# caton-d-q100.net
KiCad netlist of a schematic drawn in Altium Designer
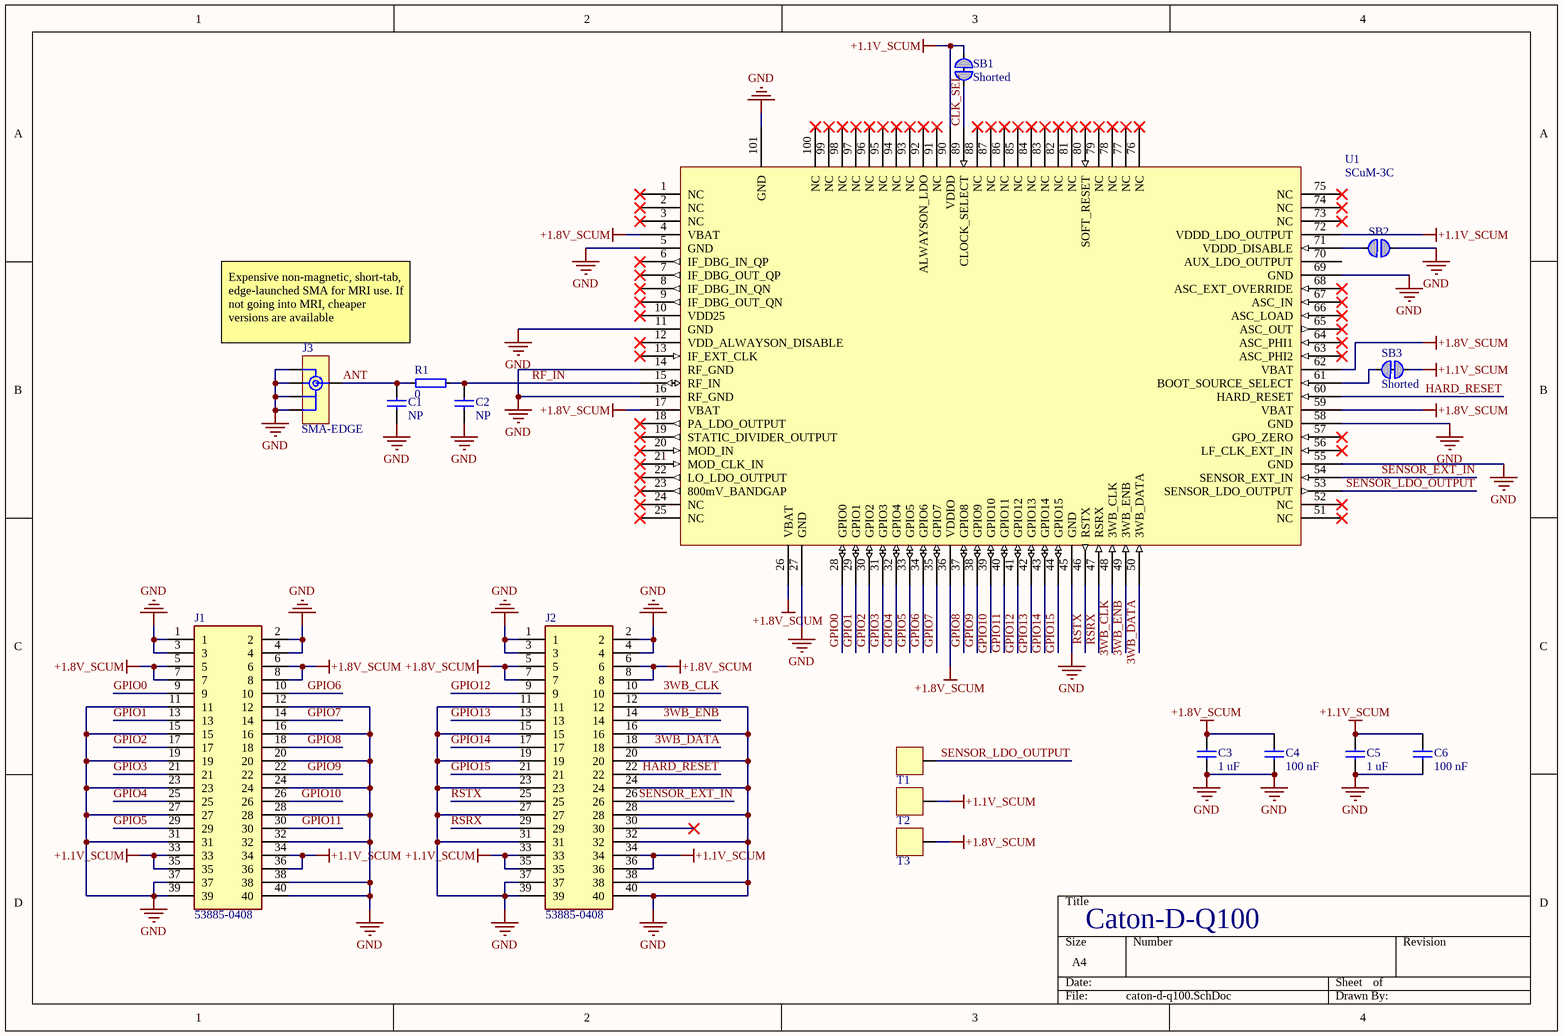
[diagram p0: caton-d-q100.SchDoc]

(export (version "E")
  (design (tool "Eeschema 10.0.6"))
  (components
    (comp (ref "C1")
      (value "NP")
      (footprint "BWRC:0603")
      (description "Capacitor, 0603, X5R, ±10%")
      (fields
        (field (name "PART NUMBER") "C0603-4µ7")
        (field (name "MANUFACTURER") "N.A.")
        (field (name "AUTHOR") "rsk")
      )
      (libsource (lib "BSAC") (part "C0603"))
    )
    (comp (ref "C2")
      (value "NP")
      (footprint "BWRC:0603")
      (description "Capacitor, 0603, X5R, ±10%")
      (fields
        (field (name "PART NUMBER") "C0603-4µ7")
        (field (name "MANUFACTURER") "N.A.")
        (field (name "AUTHOR") "rsk")
      )
      (libsource (lib "BSAC") (part "C0603"))
    )
    (comp (ref "C3")
      (value "1 uF")
      (footprint "BWRC:0603")
      (description "Capacitor, 0603, X5R, ±10%")
      (fields
        (field (name "PART NUMBER") "C0603-4µ7")
        (field (name "MANUFACTURER") "N.A.")
        (field (name "AUTHOR") "rsk")
      )
      (libsource (lib "BSAC") (part "C0603"))
    )
    (comp (ref "C4")
      (value "100 nF")
      (footprint "BWRC:0603")
      (description "Capacitor, 0603, X5R, ±10%")
      (fields
        (field (name "PART NUMBER") "C0603-4µ7")
        (field (name "MANUFACTURER") "N.A.")
        (field (name "AUTHOR") "rsk")
      )
      (libsource (lib "BSAC") (part "C0603"))
    )
    (comp (ref "C5")
      (value "1 uF")
      (footprint "BWRC:0603")
      (description "Capacitor, 0603, X5R, ±10%")
      (fields
        (field (name "PART NUMBER") "C0603-4µ7")
        (field (name "MANUFACTURER") "N.A.")
        (field (name "AUTHOR") "rsk")
      )
      (libsource (lib "BSAC") (part "C0603"))
    )
    (comp (ref "C6")
      (value "100 nF")
      (footprint "BWRC:0603")
      (description "Capacitor, 0603, X5R, ±10%")
      (fields
        (field (name "PART NUMBER") "C0603-4µ7")
        (field (name "MANUFACTURER") "N.A.")
        (field (name "AUTHOR") "rsk")
      )
      (libsource (lib "BSAC") (part "C0603"))
    )
    (comp (ref "J1")
      (value "53885-0408")
      (footprint "SamacSys:538850408")
      (fields (field (name "MOUSER PART NUMBER") "538-53885-0408"))
      (libsource (lib "BSAC") (part "53885-0408"))
    )
    (comp (ref "J2")
      (value "53885-0408")
      (footprint "SamacSys:538850408")
      (fields (field (name "MOUSER PART NUMBER") "538-53885-0408"))
      (libsource (lib "BSAC") (part "53885-0408"))
    )
    (comp (ref "J3")
      (value "SMA-EDGE")
      (footprint "BSAC:RF2-143-T-17-50-G")
      (description "Non-Magnetic\r\nCONN SMA JACK STR 50OHM EDGE MNT")
      (libsource (lib "BSAC") (part "SMA-EDGE"))
    )
    (comp (ref "R1")
      (value "0")
      (footprint "BWRC:0603")
      (description "Resistor, 0603")
      (fields
        (field (name "PART NUMBER") "R0201-10k")
        (field (name "MANUFACTURER") "N.A.")
        (field (name "AUTHOR") "rsk")
      )
      (libsource (lib "BSAC") (part "R0603"))
    )
    (comp (ref "SB1")
      (value "Shorted")
      (footprint "BSAC:Solderbridge_Shorted")
      (description "Shorted Solderbridge")
      (fields
        (field (name "PART NUMBER") "Solderbridge Shorted")
        (field (name "MANUFACTURER") "N.A.")
        (field (name "AUTHOR") "rsk")
      )
      (libsource (lib "BSAC") (part "Solderbridge Shorted"))
    )
    (comp (ref "SB2")
      (value "Solderbridge")
      (footprint "Solderbridge")
      (fields (field (name "MANUFACTURER") "N.A.") (field (name "AUTHOR") "rsk"))
      (libsource (lib "BSAC") (part "SOLDERBRIDGE"))
    )
    (comp (ref "SB3")
      (value "Shorted")
      (footprint "BSAC:Solderbridge_Shorted")
      (description "Shorted Solderbridge")
      (fields
        (field (name "PART NUMBER") "Solderbridge Shorted")
        (field (name "MANUFACTURER") "N.A.")
        (field (name "AUTHOR") "rsk")
      )
      (libsource (lib "BSAC") (part "Solderbridge Shorted"))
    )
    (comp (ref "T1")
      (value "TP_VIA")
      (footprint "BSAC:TP_VIA_1MM")
      (description "Test point 1 pin")
      (libsource (lib "BSAC") (part "TP_VIA"))
    )
    (comp (ref "T2")
      (value "TP_VIA")
      (footprint "BSAC:TP_VIA_1MM")
      (description "Test point 1 pin")
      (libsource (lib "BSAC") (part "TP_VIA"))
    )
    (comp (ref "T3")
      (value "TP_VIA")
      (footprint "BSAC:TP_VIA_1MM")
      (description "Test point 1 pin")
      (libsource (lib "BSAC") (part "TP_VIA"))
    )
    (comp (ref "U1")
      (value "SCuM-3C")
      (footprint "BSAC:QFN40P1200X1200X100_HS-101N")
      (libsource (lib "BSAC") (part "SCuM-3C"))
    )
  )
  (nets
    (net (code "1") (name "+1.1V_SCUM") (class "Default")
      (node (ref "C5") (pin "2") (pinfunction "2_2") (pintype "passive"))
      (node (ref "C6") (pin "2") (pinfunction "2_2") (pintype "passive"))
      (node (ref "J1") (pin "33") (pinfunction "33_33") (pintype "passive"))
      (node (ref "J1") (pin "34") (pinfunction "34_34") (pintype "passive"))
      (node (ref "J1") (pin "35") (pinfunction "35_35") (pintype "passive"))
      (node (ref "J1") (pin "36") (pinfunction "36_36") (pintype "passive"))
      (node (ref "J2") (pin "33") (pinfunction "33_33") (pintype "passive"))
      (node (ref "J2") (pin "34") (pinfunction "34_34") (pintype "passive"))
      (node (ref "J2") (pin "35") (pinfunction "35_35") (pintype "passive"))
      (node (ref "J2") (pin "36") (pinfunction "36_36") (pintype "passive"))
      (node (ref "SB1") (pin "1") (pinfunction "0_1") (pintype "passive"))
      (node (ref "SB3") (pin "2") (pinfunction "1_2") (pintype "passive"))
      (node (ref "T2") (pin "1") (pinfunction "1_1") (pintype "passive"))
      (node (ref "U1") (pin "72") (pinfunction "VDDD_LDO_OUTPUT_72") (pintype "power_in"))
      (node (ref "U1") (pin "90") (pinfunction "VDDD_90") (pintype "power_in"))
    )
    (net (code "2") (name "+1.8V_SCUM") (class "Default")
      (node (ref "C3") (pin "2") (pinfunction "2_2") (pintype "passive"))
      (node (ref "C4") (pin "2") (pinfunction "2_2") (pintype "passive"))
      (node (ref "J1") (pin "5") (pinfunction "5_5") (pintype "passive"))
      (node (ref "J1") (pin "6") (pinfunction "6_6") (pintype "passive"))
      (node (ref "J1") (pin "7") (pinfunction "7_7") (pintype "passive"))
      (node (ref "J1") (pin "8") (pinfunction "8_8") (pintype "passive"))
      (node (ref "J2") (pin "5") (pinfunction "5_5") (pintype "passive"))
      (node (ref "J2") (pin "6") (pinfunction "6_6") (pintype "passive"))
      (node (ref "J2") (pin "7") (pinfunction "7_7") (pintype "passive"))
      (node (ref "J2") (pin "8") (pinfunction "8_8") (pintype "passive"))
      (node (ref "T3") (pin "1") (pinfunction "1_1") (pintype "passive"))
      (node (ref "U1") (pin "17") (pinfunction "VBAT_17") (pintype "power_in"))
      (node (ref "U1") (pin "26") (pinfunction "VBAT_26") (pintype "power_in"))
      (node (ref "U1") (pin "36") (pinfunction "VDDIO_36") (pintype "power_in"))
      (node (ref "U1") (pin "4") (pinfunction "VBAT_4") (pintype "power_in"))
      (node (ref "U1") (pin "59") (pinfunction "VBAT_59") (pintype "power_in"))
      (node (ref "U1") (pin "62") (pinfunction "VBAT_62") (pintype "power_in"))
    )
    (net (code "3") (name "/3WB_CLK") (class "Default")
      (node (ref "J2") (pin "10") (pinfunction "10_10") (pintype "passive"))
      (node (ref "U1") (pin "48") (pinfunction "3WB_CLK_48") (pintype "input"))
    )
    (net (code "4") (name "/3WB_DATA") (class "Default")
      (node (ref "J2") (pin "18") (pinfunction "18_18") (pintype "passive"))
      (node (ref "U1") (pin "50") (pinfunction "3WB_DATA_50") (pintype "input"))
    )
    (net (code "5") (name "/3WB_ENB") (class "Default")
      (node (ref "J2") (pin "14") (pinfunction "14_14") (pintype "passive"))
      (node (ref "U1") (pin "49") (pinfunction "3WB_ENB_49") (pintype "input"))
    )
    (net (code "6") (name "/ANT") (class "Default")
      (node (ref "C1") (pin "2") (pinfunction "2_2") (pintype "passive"))
      (node (ref "J3") (pin "1") (pinfunction "1_1") (pintype "passive"))
      (node (ref "R1") (pin "1") (pinfunction "1_1") (pintype "passive"))
    )
    (net (code "7") (name "/CLK_SEL") (class "Default")
      (node (ref "SB1") (pin "2") (pinfunction "1_2") (pintype "passive"))
      (node (ref "U1") (pin "89") (pinfunction "CLOCK_SELECT_89") (pintype "input"))
    )
    (net (code "8") (name "/GPIO0") (class "Default")
      (node (ref "J1") (pin "9") (pinfunction "9_9") (pintype "passive"))
      (node (ref "U1") (pin "28") (pinfunction "GPIO0_28") (pintype "bidirectional"))
    )
    (net (code "9") (name "/GPIO1") (class "Default")
      (node (ref "J1") (pin "13") (pinfunction "13_13") (pintype "passive"))
      (node (ref "U1") (pin "29") (pinfunction "GPIO1_29") (pintype "bidirectional"))
    )
    (net (code "10") (name "/GPIO2") (class "Default")
      (node (ref "J1") (pin "17") (pinfunction "17_17") (pintype "passive"))
      (node (ref "U1") (pin "30") (pinfunction "GPIO2_30") (pintype "bidirectional"))
    )
    (net (code "11") (name "/GPIO3") (class "Default")
      (node (ref "J1") (pin "21") (pinfunction "21_21") (pintype "passive"))
      (node (ref "U1") (pin "31") (pinfunction "GPIO3_31") (pintype "bidirectional"))
    )
    (net (code "12") (name "/GPIO4") (class "Default")
      (node (ref "J1") (pin "25") (pinfunction "25_25") (pintype "passive"))
      (node (ref "U1") (pin "32") (pinfunction "GPIO4_32") (pintype "bidirectional"))
    )
    (net (code "13") (name "/GPIO5") (class "Default")
      (node (ref "J1") (pin "29") (pinfunction "29_29") (pintype "passive"))
      (node (ref "U1") (pin "33") (pinfunction "GPIO5_33") (pintype "bidirectional"))
    )
    (net (code "14") (name "/GPIO6") (class "Default")
      (node (ref "J1") (pin "10") (pinfunction "10_10") (pintype "passive"))
      (node (ref "U1") (pin "34") (pinfunction "GPIO6_34") (pintype "bidirectional"))
    )
    (net (code "15") (name "/GPIO7") (class "Default")
      (node (ref "J1") (pin "14") (pinfunction "14_14") (pintype "passive"))
      (node (ref "U1") (pin "35") (pinfunction "GPIO7_35") (pintype "bidirectional"))
    )
    (net (code "16") (name "/GPIO8") (class "Default")
      (node (ref "J1") (pin "18") (pinfunction "18_18") (pintype "passive"))
      (node (ref "U1") (pin "37") (pinfunction "GPIO8_37") (pintype "bidirectional"))
    )
    (net (code "17") (name "/GPIO9") (class "Default")
      (node (ref "J1") (pin "22") (pinfunction "22_22") (pintype "passive"))
      (node (ref "U1") (pin "38") (pinfunction "GPIO9_38") (pintype "bidirectional"))
    )
    (net (code "18") (name "/GPIO10") (class "Default")
      (node (ref "J1") (pin "26") (pinfunction "26_26") (pintype "passive"))
      (node (ref "U1") (pin "39") (pinfunction "GPIO10_39") (pintype "bidirectional"))
    )
    (net (code "19") (name "/GPIO11") (class "Default")
      (node (ref "J1") (pin "30") (pinfunction "30_30") (pintype "passive"))
      (node (ref "U1") (pin "40") (pinfunction "GPIO11_40") (pintype "bidirectional"))
    )
    (net (code "20") (name "/GPIO12") (class "Default")
      (node (ref "J2") (pin "9") (pinfunction "9_9") (pintype "passive"))
      (node (ref "U1") (pin "41") (pinfunction "GPIO12_41") (pintype "bidirectional"))
    )
    (net (code "21") (name "/GPIO13") (class "Default")
      (node (ref "J2") (pin "13") (pinfunction "13_13") (pintype "passive"))
      (node (ref "U1") (pin "42") (pinfunction "GPIO13_42") (pintype "bidirectional"))
    )
    (net (code "22") (name "/GPIO14") (class "Default")
      (node (ref "J2") (pin "17") (pinfunction "17_17") (pintype "passive"))
      (node (ref "U1") (pin "43") (pinfunction "GPIO14_43") (pintype "bidirectional"))
    )
    (net (code "23") (name "/GPIO15") (class "Default")
      (node (ref "J2") (pin "21") (pinfunction "21_21") (pintype "passive"))
      (node (ref "U1") (pin "44") (pinfunction "GPIO15_44") (pintype "bidirectional"))
    )
    (net (code "24") (name "/HARD_RESET") (class "Default")
      (node (ref "J2") (pin "22") (pinfunction "22_22") (pintype "passive"))
      (node (ref "U1") (pin "60") (pinfunction "HARD_RESET_60") (pintype "input"))
    )
    (net (code "25") (name "/RF_IN") (class "Default")
      (node (ref "C2") (pin "2") (pinfunction "2_2") (pintype "passive"))
      (node (ref "R1") (pin "2") (pinfunction "2_2") (pintype "passive"))
      (node (ref "U1") (pin "15") (pinfunction "RF_IN_15") (pintype "bidirectional"))
    )
    (net (code "26") (name "/RSRX") (class "Default")
      (node (ref "J2") (pin "29") (pinfunction "29_29") (pintype "passive"))
      (node (ref "U1") (pin "47") (pinfunction "RSRX_47") (pintype "input"))
    )
    (net (code "27") (name "/RSTX") (class "Default")
      (node (ref "J2") (pin "25") (pinfunction "25_25") (pintype "passive"))
      (node (ref "U1") (pin "46") (pinfunction "RSTX_46") (pintype "output"))
    )
    (net (code "28") (name "/SENSOR_EXT_IN") (class "Default")
      (node (ref "J2") (pin "26") (pinfunction "26_26") (pintype "passive"))
      (node (ref "U1") (pin "54") (pinfunction "SENSOR_EXT_IN_54") (pintype "input"))
    )
    (net (code "29") (name "/SENSOR_LDO_OUTPUT") (class "Default")
      (node (ref "T1") (pin "1") (pinfunction "1_1") (pintype "passive"))
      (node (ref "U1") (pin "53") (pinfunction "SENSOR_LDO_OUTPUT_53") (pintype "output"))
    )
    (net (code "30") (name "GND") (class "Default")
      (node (ref "C1") (pin "1") (pinfunction "1_1") (pintype "passive"))
      (node (ref "C2") (pin "1") (pinfunction "1_1") (pintype "passive"))
      (node (ref "C3") (pin "1") (pinfunction "1_1") (pintype "passive"))
      (node (ref "C4") (pin "1") (pinfunction "1_1") (pintype "passive"))
      (node (ref "C5") (pin "1") (pinfunction "1_1") (pintype "passive"))
      (node (ref "C6") (pin "1") (pinfunction "1_1") (pintype "passive"))
      (node (ref "J1") (pin "1") (pinfunction "1_1") (pintype "passive"))
      (node (ref "J1") (pin "11") (pinfunction "11_11") (pintype "passive"))
      (node (ref "J1") (pin "12") (pinfunction "12_12") (pintype "passive"))
      (node (ref "J1") (pin "15") (pinfunction "15_15") (pintype "passive"))
      (node (ref "J1") (pin "16") (pinfunction "16_16") (pintype "passive"))
      (node (ref "J1") (pin "19") (pinfunction "19_19") (pintype "passive"))
      (node (ref "J1") (pin "2") (pinfunction "2_2") (pintype "passive"))
      (node (ref "J1") (pin "20") (pinfunction "20_20") (pintype "passive"))
      (node (ref "J1") (pin "23") (pinfunction "23_23") (pintype "passive"))
      (node (ref "J1") (pin "24") (pinfunction "24_24") (pintype "passive"))
      (node (ref "J1") (pin "27") (pinfunction "27_27") (pintype "passive"))
      (node (ref "J1") (pin "28") (pinfunction "28_28") (pintype "passive"))
      (node (ref "J1") (pin "3") (pinfunction "3_3") (pintype "passive"))
      (node (ref "J1") (pin "31") (pinfunction "31_31") (pintype "passive"))
      (node (ref "J1") (pin "32") (pinfunction "32_32") (pintype "passive"))
      (node (ref "J1") (pin "37") (pinfunction "37_37") (pintype "passive"))
      (node (ref "J1") (pin "38") (pinfunction "38_38") (pintype "passive"))
      (node (ref "J1") (pin "39") (pinfunction "39_39") (pintype "passive"))
      (node (ref "J1") (pin "4") (pinfunction "4_4") (pintype "passive"))
      (node (ref "J1") (pin "40") (pinfunction "40_40") (pintype "passive"))
      (node (ref "J2") (pin "1") (pinfunction "1_1") (pintype "passive"))
      (node (ref "J2") (pin "11") (pinfunction "11_11") (pintype "passive"))
      (node (ref "J2") (pin "12") (pinfunction "12_12") (pintype "passive"))
      (node (ref "J2") (pin "15") (pinfunction "15_15") (pintype "passive"))
      (node (ref "J2") (pin "16") (pinfunction "16_16") (pintype "passive"))
      (node (ref "J2") (pin "19") (pinfunction "19_19") (pintype "passive"))
      (node (ref "J2") (pin "2") (pinfunction "2_2") (pintype "passive"))
      (node (ref "J2") (pin "20") (pinfunction "20_20") (pintype "passive"))
      (node (ref "J2") (pin "23") (pinfunction "23_23") (pintype "passive"))
      (node (ref "J2") (pin "24") (pinfunction "24_24") (pintype "passive"))
      (node (ref "J2") (pin "27") (pinfunction "27_27") (pintype "passive"))
      (node (ref "J2") (pin "28") (pinfunction "28_28") (pintype "passive"))
      (node (ref "J2") (pin "3") (pinfunction "3_3") (pintype "passive"))
      (node (ref "J2") (pin "31") (pinfunction "31_31") (pintype "passive"))
      (node (ref "J2") (pin "32") (pinfunction "32_32") (pintype "passive"))
      (node (ref "J2") (pin "37") (pinfunction "37_37") (pintype "passive"))
      (node (ref "J2") (pin "38") (pinfunction "38_38") (pintype "passive"))
      (node (ref "J2") (pin "39") (pinfunction "39_39") (pintype "passive"))
      (node (ref "J2") (pin "4") (pinfunction "4_4") (pintype "passive"))
      (node (ref "J2") (pin "40") (pinfunction "40_40") (pintype "passive"))
      (node (ref "J3") (pin "2") (pinfunction "2_2") (pintype "passive"))
      (node (ref "J3") (pin "3") (pinfunction "3_3") (pintype "passive"))
      (node (ref "J3") (pin "4") (pinfunction "4_4") (pintype "passive"))
      (node (ref "J3") (pin "5") (pinfunction "5_5") (pintype "passive"))
      (node (ref "SB2") (pin "2") (pinfunction "1_2") (pintype "passive"))
      (node (ref "U1") (pin "101") (pinfunction "GND_101") (pintype "power_in"))
      (node (ref "U1") (pin "11") (pinfunction "GND_11") (pintype "power_in"))
      (node (ref "U1") (pin "14") (pinfunction "RF_GND_14") (pintype "power_in"))
      (node (ref "U1") (pin "16") (pinfunction "RF_GND_16") (pintype "power_in"))
      (node (ref "U1") (pin "27") (pinfunction "GND_27") (pintype "power_in"))
      (node (ref "U1") (pin "45") (pinfunction "GND_45") (pintype "power_in"))
      (node (ref "U1") (pin "5") (pinfunction "GND_5") (pintype "power_in"))
      (node (ref "U1") (pin "55") (pinfunction "GND_55") (pintype "power_in"))
      (node (ref "U1") (pin "58") (pinfunction "GND_58") (pintype "power_in"))
      (node (ref "U1") (pin "69") (pinfunction "GND_69") (pintype "power_in"))
    )
    (net (code "31") (name "Net-(SB2-0)") (class "Default")
      (node (ref "SB2") (pin "1") (pinfunction "0_1") (pintype "passive"))
      (node (ref "U1") (pin "71") (pinfunction "VDDD_DISABLE_71") (pintype "input"))
    )
    (net (code "32") (name "Net-(SB3-0)") (class "Default")
      (node (ref "SB3") (pin "1") (pinfunction "0_1") (pintype "passive"))
      (node (ref "U1") (pin "61") (pinfunction "BOOT_SOURCE_SELECT_61") (pintype "input"))
    )
    (net (code "33") (name "unconnected-(J2-Pad30)") (class "Default")
      (node (ref "J2") (pin "30") (pinfunction "30_30") (pintype "passive+no_connect"))
    )
    (net (code "34") (name "unconnected-(U1-800mV_BANDGAP-Pad23)") (class "Default")
      (node (ref "U1") (pin "23") (pinfunction "800mV_BANDGAP_23") (pintype "output+no_connect"))
    )
    (net (code "35") (name "unconnected-(U1-ALWAYSON_LDO-Pad92)") (class "Default")
      (node (ref "U1") (pin "92") (pinfunction "ALWAYSON_LDO_92") (pintype "power_in+no_connect"))
    )
    (net (code "36") (name "unconnected-(U1-ASC_EXT_OVERRIDE-Pad68)") (class "Default")
      (node (ref "U1") (pin "68") (pinfunction "ASC_EXT_OVERRIDE_68") (pintype "input+no_connect"))
    )
    (net (code "37") (name "unconnected-(U1-ASC_IN-Pad67)") (class "Default")
      (node (ref "U1") (pin "67") (pinfunction "ASC_IN_67") (pintype "input+no_connect"))
    )
    (net (code "38") (name "unconnected-(U1-ASC_LOAD-Pad66)") (class "Default")
      (node (ref "U1") (pin "66") (pinfunction "ASC_LOAD_66") (pintype "input+no_connect"))
    )
    (net (code "39") (name "unconnected-(U1-ASC_OUT-Pad65)") (class "Default")
      (node (ref "U1") (pin "65") (pinfunction "ASC_OUT_65") (pintype "output+no_connect"))
    )
    (net (code "40") (name "unconnected-(U1-ASC_PHI1-Pad64)") (class "Default")
      (node (ref "U1") (pin "64") (pinfunction "ASC_PHI1_64") (pintype "input+no_connect"))
    )
    (net (code "41") (name "unconnected-(U1-ASC_PHI2-Pad63)") (class "Default")
      (node (ref "U1") (pin "63") (pinfunction "ASC_PHI2_63") (pintype "input+no_connect"))
    )
    (net (code "42") (name "unconnected-(U1-AUX_LDO_OUTPUT-Pad70)") (class "Default")
      (node (ref "U1") (pin "70") (pinfunction "AUX_LDO_OUTPUT_70") (pintype "power_in"))
    )
    (net (code "43") (name "unconnected-(U1-GPO_ZERO-Pad57)") (class "Default")
      (node (ref "U1") (pin "57") (pinfunction "GPO_ZERO_57") (pintype "input+no_connect"))
    )
    (net (code "44") (name "unconnected-(U1-IF_DBG_IN_QN-Pad8)") (class "Default")
      (node (ref "U1") (pin "8") (pinfunction "IF_DBG_IN_QN_8") (pintype "output+no_connect"))
    )
    (net (code "45") (name "unconnected-(U1-IF_DBG_IN_QP-Pad6)") (class "Default")
      (node (ref "U1") (pin "6") (pinfunction "IF_DBG_IN_QP_6") (pintype "output+no_connect"))
    )
    (net (code "46") (name "unconnected-(U1-IF_DBG_OUT_QN-Pad9)") (class "Default")
      (node (ref "U1") (pin "9") (pinfunction "IF_DBG_OUT_QN_9") (pintype "output+no_connect"))
    )
    (net (code "47") (name "unconnected-(U1-IF_DBG_OUT_QP-Pad7)") (class "Default")
      (node (ref "U1") (pin "7") (pinfunction "IF_DBG_OUT_QP_7") (pintype "output+no_connect"))
    )
    (net (code "48") (name "unconnected-(U1-IF_EXT_CLK-Pad13)") (class "Default")
      (node (ref "U1") (pin "13") (pinfunction "IF_EXT_CLK_13") (pintype "input+no_connect"))
    )
    (net (code "49") (name "unconnected-(U1-LF_CLK_EXT_IN-Pad56)") (class "Default")
      (node (ref "U1") (pin "56") (pinfunction "LF_CLK_EXT_IN_56") (pintype "input+no_connect"))
    )
    (net (code "50") (name "unconnected-(U1-LO_LDO_OUTPUT-Pad22)") (class "Default")
      (node (ref "U1") (pin "22") (pinfunction "LO_LDO_OUTPUT_22") (pintype "output+no_connect"))
    )
    (net (code "51") (name "unconnected-(U1-MOD_CLK_IN-Pad21)") (class "Default")
      (node (ref "U1") (pin "21") (pinfunction "MOD_CLK_IN_21") (pintype "input+no_connect"))
    )
    (net (code "52") (name "unconnected-(U1-MOD_IN-Pad20)") (class "Default")
      (node (ref "U1") (pin "20") (pinfunction "MOD_IN_20") (pintype "input+no_connect"))
    )
    (net (code "53") (name "unconnected-(U1-NC-Pad1)") (class "Default")
      (node (ref "U1") (pin "1") (pinfunction "NC_1") (pintype "passive+no_connect"))
    )
    (net (code "54") (name "unconnected-(U1-NC-Pad2)") (class "Default")
      (node (ref "U1") (pin "2") (pinfunction "NC_2") (pintype "passive+no_connect"))
    )
    (net (code "55") (name "unconnected-(U1-NC-Pad3)") (class "Default")
      (node (ref "U1") (pin "3") (pinfunction "NC_3") (pintype "passive+no_connect"))
    )
    (net (code "56") (name "unconnected-(U1-NC-Pad24)") (class "Default")
      (node (ref "U1") (pin "24") (pinfunction "NC_24") (pintype "passive+no_connect"))
    )
    (net (code "57") (name "unconnected-(U1-NC-Pad25)") (class "Default")
      (node (ref "U1") (pin "25") (pinfunction "NC_25") (pintype "passive+no_connect"))
    )
    (net (code "58") (name "unconnected-(U1-NC-Pad51)") (class "Default")
      (node (ref "U1") (pin "51") (pinfunction "NC_51") (pintype "passive+no_connect"))
    )
    (net (code "59") (name "unconnected-(U1-NC-Pad52)") (class "Default")
      (node (ref "U1") (pin "52") (pinfunction "NC_52") (pintype "passive+no_connect"))
    )
    (net (code "60") (name "unconnected-(U1-NC-Pad73)") (class "Default")
      (node (ref "U1") (pin "73") (pinfunction "NC_73") (pintype "passive+no_connect"))
    )
    (net (code "61") (name "unconnected-(U1-NC-Pad74)") (class "Default")
      (node (ref "U1") (pin "74") (pinfunction "NC_74") (pintype "passive+no_connect"))
    )
    (net (code "62") (name "unconnected-(U1-NC-Pad75)") (class "Default")
      (node (ref "U1") (pin "75") (pinfunction "NC_75") (pintype "passive+no_connect"))
    )
    (net (code "63") (name "unconnected-(U1-NC-Pad76)") (class "Default")
      (node (ref "U1") (pin "76") (pinfunction "NC_76") (pintype "passive+no_connect"))
    )
    (net (code "64") (name "unconnected-(U1-NC-Pad77)") (class "Default")
      (node (ref "U1") (pin "77") (pinfunction "NC_77") (pintype "passive+no_connect"))
    )
    (net (code "65") (name "unconnected-(U1-NC-Pad78)") (class "Default")
      (node (ref "U1") (pin "78") (pinfunction "NC_78") (pintype "passive+no_connect"))
    )
    (net (code "66") (name "unconnected-(U1-NC-Pad79)") (class "Default")
      (node (ref "U1") (pin "79") (pinfunction "NC_79") (pintype "passive+no_connect"))
    )
    (net (code "67") (name "unconnected-(U1-NC-Pad81)") (class "Default")
      (node (ref "U1") (pin "81") (pinfunction "NC_81") (pintype "passive+no_connect"))
    )
    (net (code "68") (name "unconnected-(U1-NC-Pad82)") (class "Default")
      (node (ref "U1") (pin "82") (pinfunction "NC_82") (pintype "passive+no_connect"))
    )
    (net (code "69") (name "unconnected-(U1-NC-Pad83)") (class "Default")
      (node (ref "U1") (pin "83") (pinfunction "NC_83") (pintype "passive+no_connect"))
    )
    (net (code "70") (name "unconnected-(U1-NC-Pad84)") (class "Default")
      (node (ref "U1") (pin "84") (pinfunction "NC_84") (pintype "passive+no_connect"))
    )
    (net (code "71") (name "unconnected-(U1-NC-Pad85)") (class "Default")
      (node (ref "U1") (pin "85") (pinfunction "NC_85") (pintype "passive+no_connect"))
    )
    (net (code "72") (name "unconnected-(U1-NC-Pad86)") (class "Default")
      (node (ref "U1") (pin "86") (pinfunction "NC_86") (pintype "passive+no_connect"))
    )
    (net (code "73") (name "unconnected-(U1-NC-Pad87)") (class "Default")
      (node (ref "U1") (pin "87") (pinfunction "NC_87") (pintype "passive+no_connect"))
    )
    (net (code "74") (name "unconnected-(U1-NC-Pad88)") (class "Default")
      (node (ref "U1") (pin "88") (pinfunction "NC_88") (pintype "passive+no_connect"))
    )
    (net (code "75") (name "unconnected-(U1-NC-Pad91)") (class "Default")
      (node (ref "U1") (pin "91") (pinfunction "NC_91") (pintype "passive+no_connect"))
    )
    (net (code "76") (name "unconnected-(U1-NC-Pad93)") (class "Default")
      (node (ref "U1") (pin "93") (pinfunction "NC_93") (pintype "passive+no_connect"))
    )
    (net (code "77") (name "unconnected-(U1-NC-Pad94)") (class "Default")
      (node (ref "U1") (pin "94") (pinfunction "NC_94") (pintype "passive+no_connect"))
    )
    (net (code "78") (name "unconnected-(U1-NC-Pad95)") (class "Default")
      (node (ref "U1") (pin "95") (pinfunction "NC_95") (pintype "passive+no_connect"))
    )
    (net (code "79") (name "unconnected-(U1-NC-Pad96)") (class "Default")
      (node (ref "U1") (pin "96") (pinfunction "NC_96") (pintype "passive+no_connect"))
    )
    (net (code "80") (name "unconnected-(U1-NC-Pad97)") (class "Default")
      (node (ref "U1") (pin "97") (pinfunction "NC_97") (pintype "passive+no_connect"))
    )
    (net (code "81") (name "unconnected-(U1-NC-Pad98)") (class "Default")
      (node (ref "U1") (pin "98") (pinfunction "NC_98") (pintype "passive+no_connect"))
    )
    (net (code "82") (name "unconnected-(U1-NC-Pad99)") (class "Default")
      (node (ref "U1") (pin "99") (pinfunction "NC_99") (pintype "passive+no_connect"))
    )
    (net (code "83") (name "unconnected-(U1-NC-Pad100)") (class "Default")
      (node (ref "U1") (pin "100") (pinfunction "NC_100") (pintype "passive+no_connect"))
    )
    (net (code "84") (name "unconnected-(U1-PA_LDO_OUTPUT-Pad18)") (class "Default")
      (node (ref "U1") (pin "18") (pinfunction "PA_LDO_OUTPUT_18") (pintype "output+no_connect"))
    )
    (net (code "85") (name "unconnected-(U1-SOFT_RESET-Pad80)") (class "Default")
      (node (ref "U1") (pin "80") (pinfunction "SOFT_RESET_80") (pintype "input+no_connect"))
    )
    (net (code "86") (name "unconnected-(U1-STATIC_DIVIDER_OUTPUT-Pad19)") (class "Default")
      (node (ref "U1") (pin "19") (pinfunction "STATIC_DIVIDER_OUTPUT_19") (pintype "output+no_connect"))
    )
    (net (code "87") (name "unconnected-(U1-VDD25-Pad10)") (class "Default")
      (node (ref "U1") (pin "10") (pinfunction "VDD25_10") (pintype "power_in+no_connect"))
    )
    (net (code "88") (name "unconnected-(U1-VDD_ALWAYSON_DISABLE-Pad12)") (class "Default")
      (node (ref "U1") (pin "12") (pinfunction "VDD_ALWAYSON_DISABLE_12") (pintype "power_in+no_connect"))
    )
  )
)
